# draftBoard.net
KiCad netlist of a schematic drawn in EAGLE
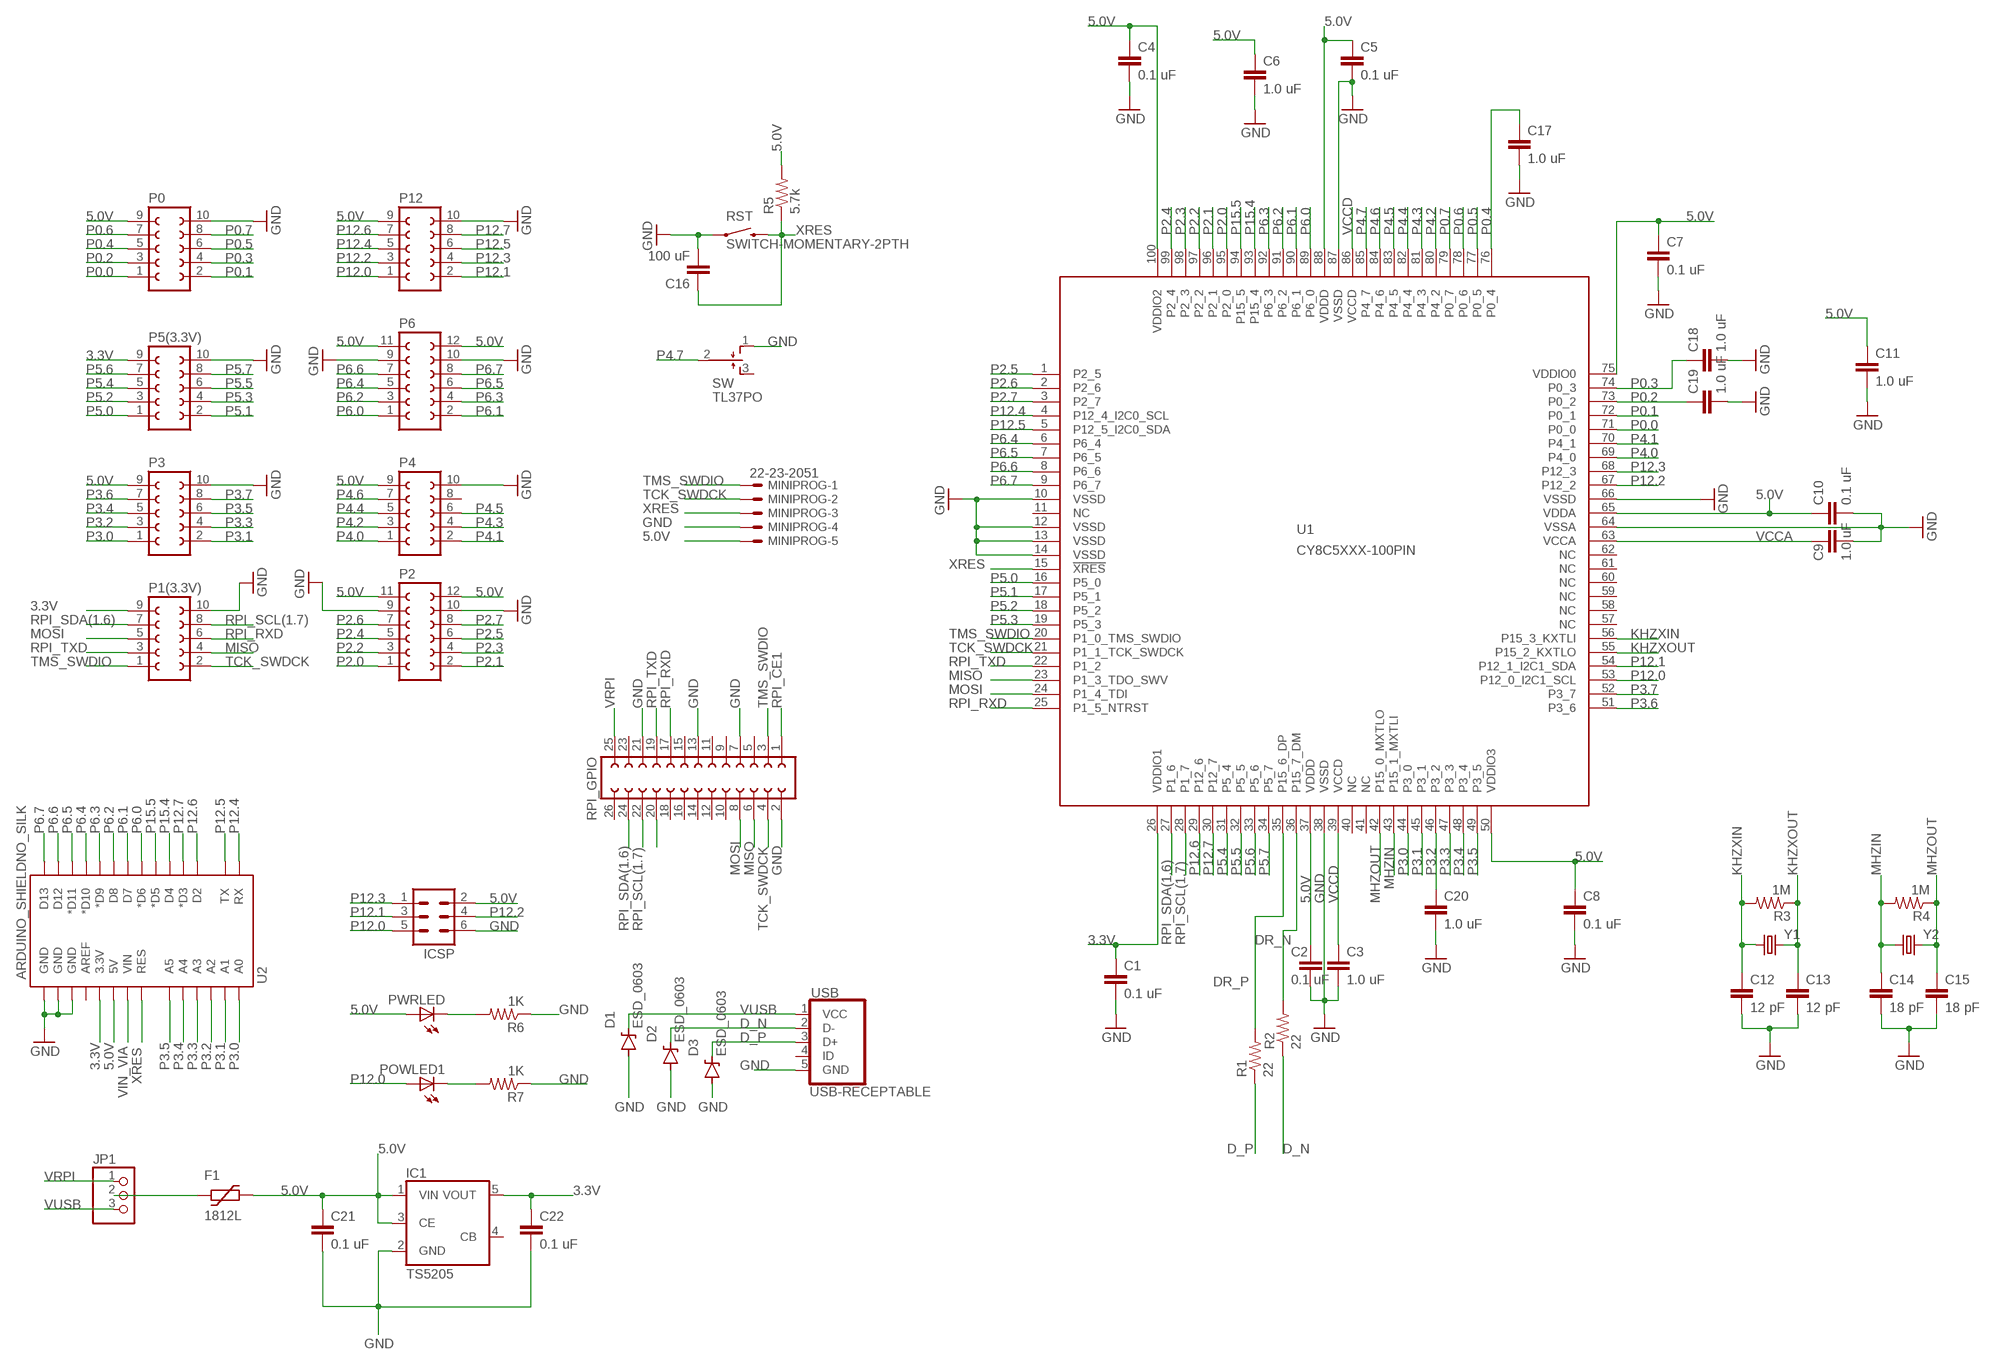
[diagram p0: schematic, sheet 1]

(export (version "E")
  (design (tool "Eeschema 10.0.6"))
  (components
    (comp (ref "C1")
      (value "0.1 uF")
      (footprint "eagle-import:0603-CAP@1")
      (libsource (lib "eagle-import") (part "CAP0603-CAP"))
    )
    (comp (ref "C2")
      (value "0.1 uF")
      (footprint "eagle-import:0603-CAP@1")
      (libsource (lib "eagle-import") (part "CAP0603-CAP"))
    )
    (comp (ref "C3")
      (value "1.0 uF")
      (footprint "eagle-import:0603-CAP@1")
      (libsource (lib "eagle-import") (part "CAP0603-CAP"))
    )
    (comp (ref "C4")
      (value "0.1 uF")
      (footprint "eagle-import:0603-CAP@1")
      (libsource (lib "eagle-import") (part "CAP0603-CAP"))
    )
    (comp (ref "C5")
      (value "0.1 uF")
      (footprint "eagle-import:0603-CAP@1")
      (libsource (lib "eagle-import") (part "CAP0603-CAP"))
    )
    (comp (ref "C6")
      (value "1.0 uF")
      (footprint "eagle-import:0603-CAP@1")
      (libsource (lib "eagle-import") (part "CAP0603-CAP"))
    )
    (comp (ref "C7")
      (value "0.1 uF")
      (footprint "eagle-import:0603-CAP@1")
      (libsource (lib "eagle-import") (part "CAP0603-CAP"))
    )
    (comp (ref "C8")
      (value "0.1 uF")
      (footprint "eagle-import:0603-CAP@1")
      (libsource (lib "eagle-import") (part "CAP0603-CAP"))
    )
    (comp (ref "C9")
      (value "1.0 uF")
      (footprint "eagle-import:0603-CAP@1")
      (libsource (lib "eagle-import") (part "CAP0603-CAP"))
    )
    (comp (ref "C10")
      (value "0.1 uF")
      (footprint "eagle-import:0603-CAP@1")
      (libsource (lib "eagle-import") (part "CAP0603-CAP"))
    )
    (comp (ref "C11")
      (value "1.0 uF")
      (footprint "eagle-import:0603-CAP@1")
      (libsource (lib "eagle-import") (part "CAP0603-CAP"))
    )
    (comp (ref "C12")
      (value "12 pF")
      (footprint "eagle-import:0603-CAP@1")
      (libsource (lib "eagle-import") (part "CAP0603-CAP"))
    )
    (comp (ref "C13")
      (value "12 pF")
      (footprint "eagle-import:0603-CAP@1")
      (libsource (lib "eagle-import") (part "CAP0603-CAP"))
    )
    (comp (ref "C14")
      (value "18 pF")
      (footprint "eagle-import:0603-CAP@1")
      (libsource (lib "eagle-import") (part "CAP0603-CAP"))
    )
    (comp (ref "C15")
      (value "18 pF")
      (footprint "eagle-import:0603-CAP@1")
      (libsource (lib "eagle-import") (part "CAP0603-CAP"))
    )
    (comp (ref "C16")
      (value "100 uF")
      (footprint "eagle-import:0603-CAP@1")
      (libsource (lib "eagle-import") (part "CAP0603-CAP"))
    )
    (comp (ref "C17")
      (value "1.0 uF")
      (footprint "eagle-import:0603-CAP@1")
      (libsource (lib "eagle-import") (part "CAP0603-CAP"))
    )
    (comp (ref "C18")
      (value "1.0 uF")
      (footprint "eagle-import:0603-CAP@1")
      (libsource (lib "eagle-import") (part "CAP0603-CAP"))
    )
    (comp (ref "C19")
      (value "1.0 uF")
      (footprint "eagle-import:0603-CAP@1")
      (libsource (lib "eagle-import") (part "CAP0603-CAP"))
    )
    (comp (ref "C20")
      (value "1.0 uF")
      (footprint "eagle-import:0603-CAP@1")
      (libsource (lib "eagle-import") (part "CAP0603-CAP"))
    )
    (comp (ref "C21")
      (value "0.1 uF")
      (footprint "eagle-import:0603-CAP@1")
      (libsource (lib "eagle-import") (part "CAP0603-CAP"))
    )
    (comp (ref "C22")
      (value "0.1 uF")
      (footprint "eagle-import:0603-CAP@1")
      (libsource (lib "eagle-import") (part "CAP0603-CAP"))
    )
    (comp (ref "D1")
      (value "ESD_0603")
      (footprint "eagle-import:0603-CAP")
      (libsource (lib "eagle-import") (part "ESD_0603"))
    )
    (comp (ref "D2")
      (value "ESD_0603")
      (footprint "eagle-import:0603-CAP")
      (libsource (lib "eagle-import") (part "ESD_0603"))
    )
    (comp (ref "D3")
      (value "ESD_0603")
      (footprint "eagle-import:0603-CAP")
      (libsource (lib "eagle-import") (part "ESD_0603"))
    )
    (comp (ref "F1")
      (value "1812L")
      (footprint "eagle-import:1812L")
      (libsource (lib "eagle-import") (part "1812L"))
    )
    (comp (ref "IC1")
      (value "TS5205")
      (footprint "eagle-import:SOT25")
      (libsource (lib "eagle-import") (part "TS5205"))
    )
    (comp (ref "ICSP")
      (value "MA03-2")
      (footprint "eagle-import:MA03-2")
      (libsource (lib "eagle-import") (part "MA03-2"))
    )
    (comp (ref "JP1")
      (value "PINHD-1X3")
      (footprint "eagle-import:1X03")
      (libsource (lib "eagle-import") (part "PINHD-1X3"))
    )
    (comp (ref "MINIPROG")
      (value "22-23-2051")
      (footprint "eagle-import:22-23-2051")
      (fields (field (name "MF") "MOLEX"))
      (libsource (lib "eagle-import") (part "22-23-2051"))
    )
    (comp (ref "P0")
      (value "FE05-2")
      (footprint "eagle-import:FE05-2")
      (libsource (lib "eagle-import") (part "FE05-2"))
    )
    (comp (ref "P1(3.3V)")
      (value "FE05-2")
      (footprint "eagle-import:FE05-2")
      (libsource (lib "eagle-import") (part "FE05-2"))
    )
    (comp (ref "P2")
      (value "FE06-2")
      (footprint "eagle-import:FE06-2")
      (libsource (lib "eagle-import") (part "FE06-2"))
    )
    (comp (ref "P3")
      (value "FE05-2")
      (footprint "eagle-import:FE05-2")
      (libsource (lib "eagle-import") (part "FE05-2"))
    )
    (comp (ref "P4")
      (value "FE05-2")
      (footprint "eagle-import:FE05-2")
      (libsource (lib "eagle-import") (part "FE05-2"))
    )
    (comp (ref "P5(3.3V)")
      (value "FE05-2")
      (footprint "eagle-import:FE05-2")
      (libsource (lib "eagle-import") (part "FE05-2"))
    )
    (comp (ref "P6")
      (value "FE06-2")
      (footprint "eagle-import:FE06-2")
      (libsource (lib "eagle-import") (part "FE06-2"))
    )
    (comp (ref "P12")
      (value "FE05-2")
      (footprint "eagle-import:FE05-2")
      (libsource (lib "eagle-import") (part "FE05-2"))
    )
    (comp (ref "POWLED1")
      (value "LED0603")
      (footprint "eagle-import:LED-0603")
      (libsource (lib "eagle-import") (part "LED0603"))
    )
    (comp (ref "PWRLED")
      (value "LED0603")
      (footprint "eagle-import:LED-0603")
      (libsource (lib "eagle-import") (part "LED0603"))
    )
    (comp (ref "R1")
      (value "22")
      (footprint "eagle-import:0603-RES")
      (libsource (lib "eagle-import") (part "RESISTOR0603-RES"))
    )
    (comp (ref "R2")
      (value "22")
      (footprint "eagle-import:0603-RES")
      (libsource (lib "eagle-import") (part "RESISTOR0603-RES"))
    )
    (comp (ref "R3")
      (value "1M")
      (footprint "eagle-import:0603-RES")
      (libsource (lib "eagle-import") (part "RESISTOR0603-RES"))
    )
    (comp (ref "R4")
      (value "1M")
      (footprint "eagle-import:0603-RES")
      (libsource (lib "eagle-import") (part "RESISTOR0603-RES"))
    )
    (comp (ref "R5")
      (value "5.7k")
      (footprint "eagle-import:0603-RES")
      (libsource (lib "eagle-import") (part "RESISTOR0603-RES"))
    )
    (comp (ref "R6")
      (value "1K")
      (footprint "eagle-import:0603-RES")
      (libsource (lib "eagle-import") (part "RESISTOR0603-RES"))
    )
    (comp (ref "R7")
      (value "1K")
      (footprint "eagle-import:0603-RES")
      (libsource (lib "eagle-import") (part "RESISTOR0603-RES"))
    )
    (comp (ref "RPI_GPIO")
      (value "FE13-2")
      (footprint "eagle-import:FE13-2")
      (libsource (lib "eagle-import") (part "FE13-2"))
    )
    (comp (ref "RST")
      (value "SWITCH-MOMENTARY-2PTH")
      (footprint "eagle-import:TACTILE-PTH")
      (libsource (lib "eagle-import") (part "SWITCH-MOMENTARY-2PTH"))
    )
    (comp (ref "SW")
      (value "TL37PO")
      (footprint "eagle-import:TL3XPO")
      (libsource (lib "eagle-import") (part "TL37PO"))
    )
    (comp (ref "U1")
      (value "CY8C5XXX-100PIN")
      (footprint "eagle-import:TQFP-14X14-100")
      (fields (field (name "MPN") "CY8C5588AXI-060"))
      (libsource (lib "eagle-import") (part "CY8C5XXX-100PIN"))
    )
    (comp (ref "U2")
      (value "ARDUINO_SHIELDNO_SILK")
      (footprint "eagle-import:DUEMILANOVE_VIAS")
      (libsource (lib "eagle-import") (part "ARDUINO_SHIELDNO_SILK"))
    )
    (comp (ref "USB")
      (value "USB-RECEPTABLE")
      (footprint "eagle-import:FCI-10103594-0001LF")
      (libsource (lib "eagle-import") (part "USB-RECEPTABLE"))
    )
    (comp (ref "Y1")
      (value "CRYSTALTC26H")
      (footprint "eagle-import:TC26H")
      (libsource (lib "eagle-import") (part "CRYSTALTC26H"))
    )
    (comp (ref "Y2")
      (value "CRYSTALHC49US")
      (footprint "eagle-import:HC49US")
      (libsource (lib "eagle-import") (part "CRYSTALHC49US"))
    )
  )
  (nets
    (net (code "1") (name "/3.3V") (class "Default")
      (node (ref "C1") (pin "1") (pinfunction "1_1") (pintype "passive"))
      (node (ref "C22") (pin "1") (pinfunction "1_1") (pintype "passive"))
      (node (ref "IC1") (pin "5") (pinfunction "VOUT_5") (pintype "passive"))
      (node (ref "P1(3.3V)") (pin "9") (pinfunction "9_9") (pintype "passive"))
      (node (ref "P5(3.3V)") (pin "9") (pinfunction "9_9") (pintype "passive"))
      (node (ref "U1") (pin "26") (pinfunction "VDDIO1_26") (pintype "passive"))
      (node (ref "U2") (pin "3.3V") (pinfunction "3.3V_3.3V") (pintype "bidirectional"))
    )
    (net (code "2") (name "/5.0V") (class "Default")
      (node (ref "C10") (pin "1") (pinfunction "1_1") (pintype "passive"))
      (node (ref "C11") (pin "1") (pinfunction "1_1") (pintype "passive"))
      (node (ref "C2") (pin "1") (pinfunction "1_1") (pintype "passive"))
      (node (ref "C21") (pin "1") (pinfunction "1_1") (pintype "passive"))
      (node (ref "C4") (pin "1") (pinfunction "1_1") (pintype "passive"))
      (node (ref "C5") (pin "1") (pinfunction "1_1") (pintype "passive"))
      (node (ref "C6") (pin "1") (pinfunction "1_1") (pintype "passive"))
      (node (ref "C7") (pin "1") (pinfunction "1_1") (pintype "passive"))
      (node (ref "C8") (pin "1") (pinfunction "1_1") (pintype "passive"))
      (node (ref "F1") (pin "P$2") (pinfunction "2_P$2") (pintype "passive"))
      (node (ref "IC1") (pin "1") (pinfunction "VIN_1") (pintype "input"))
      (node (ref "IC1") (pin "3") (pinfunction "CE_3") (pintype "input"))
      (node (ref "ICSP") (pin "2") (pinfunction "2_2") (pintype "passive"))
      (node (ref "MINIPROG") (pin "5") (pinfunction "S_5") (pintype "passive"))
      (node (ref "P0") (pin "9") (pinfunction "9_9") (pintype "passive"))
      (node (ref "P12") (pin "9") (pinfunction "9_9") (pintype "passive"))
      (node (ref "P2") (pin "11") (pinfunction "11_11") (pintype "passive"))
      (node (ref "P2") (pin "12") (pinfunction "12_12") (pintype "passive"))
      (node (ref "P3") (pin "9") (pinfunction "9_9") (pintype "passive"))
      (node (ref "P4") (pin "9") (pinfunction "9_9") (pintype "passive"))
      (node (ref "P6") (pin "11") (pinfunction "11_11") (pintype "passive"))
      (node (ref "P6") (pin "12") (pinfunction "12_12") (pintype "passive"))
      (node (ref "PWRLED") (pin "A") (pinfunction "A_A") (pintype "passive"))
      (node (ref "R5") (pin "2") (pinfunction "2_2") (pintype "passive"))
      (node (ref "U1") (pin "100") (pinfunction "VDDIO2_100") (pintype "passive"))
      (node (ref "U1") (pin "37") (pinfunction "VDDD_37") (pintype "passive"))
      (node (ref "U1") (pin "50") (pinfunction "VDDIO3_50") (pintype "passive"))
      (node (ref "U1") (pin "65") (pinfunction "VDDA_65") (pintype "passive"))
      (node (ref "U1") (pin "75") (pinfunction "VDDIO0_75") (pintype "passive"))
      (node (ref "U1") (pin "88") (pinfunction "VDDD_88") (pintype "passive"))
      (node (ref "U2") (pin "5V") (pinfunction "5V_5V") (pintype "bidirectional"))
    )
    (net (code "3") (name "/DR_N") (class "Default")
      (node (ref "R2") (pin "2") (pinfunction "2_2") (pintype "passive"))
      (node (ref "U1") (pin "36") (pinfunction "P15_7_DM_36") (pintype "passive"))
    )
    (net (code "4") (name "/DR_P") (class "Default")
      (node (ref "R1") (pin "2") (pinfunction "2_2") (pintype "passive"))
      (node (ref "U1") (pin "35") (pinfunction "P15_6_DP_35") (pintype "passive"))
    )
    (net (code "5") (name "/D_N") (class "Default")
      (node (ref "D2") (pin "1") (pinfunction "C_1") (pintype "passive"))
      (node (ref "R2") (pin "1") (pinfunction "1_1") (pintype "passive"))
      (node (ref "USB") (pin "2") (pinfunction "D-_2") (pintype "bidirectional"))
    )
    (net (code "6") (name "/D_P") (class "Default")
      (node (ref "D3") (pin "1") (pinfunction "C_1") (pintype "passive"))
      (node (ref "R1") (pin "1") (pinfunction "1_1") (pintype "passive"))
      (node (ref "USB") (pin "3") (pinfunction "D+_3") (pintype "bidirectional"))
    )
    (net (code "7") (name "/KHZXIN") (class "Default")
      (node (ref "C12") (pin "1") (pinfunction "1_1") (pintype "passive"))
      (node (ref "R3") (pin "2") (pinfunction "2_2") (pintype "passive"))
      (node (ref "U1") (pin "56") (pinfunction "P15_3_KXTLI_56") (pintype "passive"))
      (node (ref "Y1") (pin "1") (pinfunction "1_1") (pintype "passive"))
    )
    (net (code "8") (name "/KHZXOUT") (class "Default")
      (node (ref "C13") (pin "1") (pinfunction "1_1") (pintype "passive"))
      (node (ref "R3") (pin "1") (pinfunction "1_1") (pintype "passive"))
      (node (ref "U1") (pin "55") (pinfunction "P15_2_KXTLO_55") (pintype "passive"))
      (node (ref "Y1") (pin "2") (pinfunction "2_2") (pintype "passive"))
    )
    (net (code "9") (name "/MHZIN") (class "Default")
      (node (ref "C14") (pin "1") (pinfunction "1_1") (pintype "passive"))
      (node (ref "R4") (pin "2") (pinfunction "2_2") (pintype "passive"))
      (node (ref "U1") (pin "43") (pinfunction "P15_1_MXTLI_43") (pintype "passive"))
      (node (ref "Y2") (pin "1") (pinfunction "1_1") (pintype "passive"))
    )
    (net (code "10") (name "/MHZOUT") (class "Default")
      (node (ref "C15") (pin "1") (pinfunction "1_1") (pintype "passive"))
      (node (ref "R4") (pin "1") (pinfunction "1_1") (pintype "passive"))
      (node (ref "U1") (pin "42") (pinfunction "P15_0_MXTLO_42") (pintype "passive"))
      (node (ref "Y2") (pin "2") (pinfunction "2_2") (pintype "passive"))
    )
    (net (code "11") (name "/MISO") (class "Default")
      (node (ref "P1(3.3V)") (pin "4") (pinfunction "4_4") (pintype "passive"))
      (node (ref "RPI_GPIO") (pin "6") (pinfunction "6_6") (pintype "passive"))
      (node (ref "U1") (pin "23") (pinfunction "P1_3_TDO_SWV_23") (pintype "passive"))
    )
    (net (code "12") (name "/MOSI") (class "Default")
      (node (ref "P1(3.3V)") (pin "5") (pinfunction "5_5") (pintype "passive"))
      (node (ref "RPI_GPIO") (pin "8") (pinfunction "8_8") (pintype "passive"))
      (node (ref "U1") (pin "24") (pinfunction "P1_4_TDI_24") (pintype "passive"))
    )
    (net (code "13") (name "/P0.0") (class "Default")
      (node (ref "P0") (pin "1") (pinfunction "1_1") (pintype "passive"))
      (node (ref "U1") (pin "71") (pinfunction "P0_0_71") (pintype "passive"))
    )
    (net (code "14") (name "/P0.1") (class "Default")
      (node (ref "P0") (pin "2") (pinfunction "2_2") (pintype "passive"))
      (node (ref "U1") (pin "72") (pinfunction "P0_1_72") (pintype "passive"))
    )
    (net (code "15") (name "/P0.2") (class "Default")
      (node (ref "C19") (pin "1") (pinfunction "1_1") (pintype "passive"))
      (node (ref "P0") (pin "3") (pinfunction "3_3") (pintype "passive"))
      (node (ref "U1") (pin "73") (pinfunction "P0_2_73") (pintype "passive"))
    )
    (net (code "16") (name "/P0.3") (class "Default")
      (node (ref "C18") (pin "1") (pinfunction "1_1") (pintype "passive"))
      (node (ref "P0") (pin "4") (pinfunction "4_4") (pintype "passive"))
      (node (ref "U1") (pin "74") (pinfunction "P0_3_74") (pintype "passive"))
    )
    (net (code "17") (name "/P0.4") (class "Default")
      (node (ref "C17") (pin "1") (pinfunction "1_1") (pintype "passive"))
      (node (ref "P0") (pin "5") (pinfunction "5_5") (pintype "passive"))
      (node (ref "U1") (pin "76") (pinfunction "P0_4_76") (pintype "passive"))
    )
    (net (code "18") (name "/P0.5") (class "Default")
      (node (ref "P0") (pin "6") (pinfunction "6_6") (pintype "passive"))
      (node (ref "U1") (pin "77") (pinfunction "P0_5_77") (pintype "passive"))
    )
    (net (code "19") (name "/P0.6") (class "Default")
      (node (ref "P0") (pin "7") (pinfunction "7_7") (pintype "passive"))
      (node (ref "U1") (pin "78") (pinfunction "P0_6_78") (pintype "passive"))
    )
    (net (code "20") (name "/P0.7") (class "Default")
      (node (ref "P0") (pin "8") (pinfunction "8_8") (pintype "passive"))
      (node (ref "U1") (pin "79") (pinfunction "P0_7_79") (pintype "passive"))
    )
    (net (code "21") (name "/P2.0") (class "Default")
      (node (ref "P2") (pin "1") (pinfunction "1_1") (pintype "passive"))
      (node (ref "U1") (pin "95") (pinfunction "P2_0_95") (pintype "passive"))
    )
    (net (code "22") (name "/P2.1") (class "Default")
      (node (ref "P2") (pin "2") (pinfunction "2_2") (pintype "passive"))
      (node (ref "U1") (pin "96") (pinfunction "P2_1_96") (pintype "passive"))
    )
    (net (code "23") (name "/P2.2") (class "Default")
      (node (ref "P2") (pin "3") (pinfunction "3_3") (pintype "passive"))
      (node (ref "U1") (pin "97") (pinfunction "P2_2_97") (pintype "passive"))
    )
    (net (code "24") (name "/P2.3") (class "Default")
      (node (ref "P2") (pin "4") (pinfunction "4_4") (pintype "passive"))
      (node (ref "U1") (pin "98") (pinfunction "P2_3_98") (pintype "passive"))
    )
    (net (code "25") (name "/P2.4") (class "Default")
      (node (ref "P2") (pin "5") (pinfunction "5_5") (pintype "passive"))
      (node (ref "U1") (pin "99") (pinfunction "P2_4_99") (pintype "passive"))
    )
    (net (code "26") (name "/P2.5") (class "Default")
      (node (ref "P2") (pin "6") (pinfunction "6_6") (pintype "passive"))
      (node (ref "U1") (pin "1") (pinfunction "P2_5_1") (pintype "passive"))
    )
    (net (code "27") (name "/P2.6") (class "Default")
      (node (ref "P2") (pin "7") (pinfunction "7_7") (pintype "passive"))
      (node (ref "U1") (pin "2") (pinfunction "P2_6_2") (pintype "passive"))
    )
    (net (code "28") (name "/P2.7") (class "Default")
      (node (ref "P2") (pin "8") (pinfunction "8_8") (pintype "passive"))
      (node (ref "U1") (pin "3") (pinfunction "P2_7_3") (pintype "passive"))
    )
    (net (code "29") (name "/P3.0") (class "Default")
      (node (ref "P3") (pin "1") (pinfunction "1_1") (pintype "passive"))
      (node (ref "U1") (pin "44") (pinfunction "P3_0_44") (pintype "passive"))
      (node (ref "U2") (pin "A0") (pinfunction "A0_A0") (pintype "bidirectional"))
    )
    (net (code "30") (name "/P3.1") (class "Default")
      (node (ref "P3") (pin "2") (pinfunction "2_2") (pintype "passive"))
      (node (ref "U1") (pin "45") (pinfunction "P3_1_45") (pintype "passive"))
      (node (ref "U2") (pin "A1") (pinfunction "A1_A1") (pintype "bidirectional"))
    )
    (net (code "31") (name "/P3.2") (class "Default")
      (node (ref "C20") (pin "1") (pinfunction "1_1") (pintype "passive"))
      (node (ref "P3") (pin "3") (pinfunction "3_3") (pintype "passive"))
      (node (ref "U1") (pin "46") (pinfunction "P3_2_46") (pintype "passive"))
      (node (ref "U2") (pin "A2") (pinfunction "A2_A2") (pintype "bidirectional"))
    )
    (net (code "32") (name "/P3.3") (class "Default")
      (node (ref "P3") (pin "4") (pinfunction "4_4") (pintype "passive"))
      (node (ref "U1") (pin "47") (pinfunction "P3_3_47") (pintype "passive"))
      (node (ref "U2") (pin "A3") (pinfunction "A3_A3") (pintype "bidirectional"))
    )
    (net (code "33") (name "/P3.4") (class "Default")
      (node (ref "P3") (pin "5") (pinfunction "5_5") (pintype "passive"))
      (node (ref "U1") (pin "48") (pinfunction "P3_4_48") (pintype "passive"))
      (node (ref "U2") (pin "A4") (pinfunction "A4_A4") (pintype "bidirectional"))
    )
    (net (code "34") (name "/P3.5") (class "Default")
      (node (ref "P3") (pin "6") (pinfunction "6_6") (pintype "passive"))
      (node (ref "U1") (pin "49") (pinfunction "P3_5_49") (pintype "passive"))
      (node (ref "U2") (pin "A5") (pinfunction "A5_A5") (pintype "bidirectional"))
    )
    (net (code "35") (name "/P3.6") (class "Default")
      (node (ref "P3") (pin "7") (pinfunction "7_7") (pintype "passive"))
      (node (ref "U1") (pin "51") (pinfunction "P3_6_51") (pintype "passive"))
    )
    (net (code "36") (name "/P3.7") (class "Default")
      (node (ref "P3") (pin "8") (pinfunction "8_8") (pintype "passive"))
      (node (ref "U1") (pin "52") (pinfunction "P3_7_52") (pintype "passive"))
    )
    (net (code "37") (name "/P4.0") (class "Default")
      (node (ref "P4") (pin "1") (pinfunction "1_1") (pintype "passive"))
      (node (ref "U1") (pin "69") (pinfunction "P4_0_69") (pintype "passive"))
    )
    (net (code "38") (name "/P4.1") (class "Default")
      (node (ref "P4") (pin "2") (pinfunction "2_2") (pintype "passive"))
      (node (ref "U1") (pin "70") (pinfunction "P4_1_70") (pintype "passive"))
    )
    (net (code "39") (name "/P4.2") (class "Default")
      (node (ref "P4") (pin "3") (pinfunction "3_3") (pintype "passive"))
      (node (ref "U1") (pin "80") (pinfunction "P4_2_80") (pintype "passive"))
    )
    (net (code "40") (name "/P4.3") (class "Default")
      (node (ref "P4") (pin "4") (pinfunction "4_4") (pintype "passive"))
      (node (ref "U1") (pin "81") (pinfunction "P4_3_81") (pintype "passive"))
    )
    (net (code "41") (name "/P4.4") (class "Default")
      (node (ref "P4") (pin "5") (pinfunction "5_5") (pintype "passive"))
      (node (ref "U1") (pin "82") (pinfunction "P4_4_82") (pintype "passive"))
    )
    (net (code "42") (name "/P4.5") (class "Default")
      (node (ref "P4") (pin "6") (pinfunction "6_6") (pintype "passive"))
      (node (ref "U1") (pin "83") (pinfunction "P4_5_83") (pintype "passive"))
    )
    (net (code "43") (name "/P4.6") (class "Default")
      (node (ref "P4") (pin "7") (pinfunction "7_7") (pintype "passive"))
      (node (ref "U1") (pin "84") (pinfunction "P4_6_84") (pintype "passive"))
    )
    (net (code "44") (name "/P4.7") (class "Default")
      (node (ref "SW") (pin "2") (pinfunction "P_2") (pintype "passive"))
      (node (ref "U1") (pin "85") (pinfunction "P4_7_85") (pintype "passive"))
    )
    (net (code "45") (name "/P5.0") (class "Default")
      (node (ref "P5(3.3V)") (pin "1") (pinfunction "1_1") (pintype "passive"))
      (node (ref "U1") (pin "16") (pinfunction "P5_0_16") (pintype "passive"))
    )
    (net (code "46") (name "/P5.1") (class "Default")
      (node (ref "P5(3.3V)") (pin "2") (pinfunction "2_2") (pintype "passive"))
      (node (ref "U1") (pin "17") (pinfunction "P5_1_17") (pintype "passive"))
    )
    (net (code "47") (name "/P5.2") (class "Default")
      (node (ref "P5(3.3V)") (pin "3") (pinfunction "3_3") (pintype "passive"))
      (node (ref "U1") (pin "18") (pinfunction "P5_2_18") (pintype "passive"))
    )
    (net (code "48") (name "/P5.3") (class "Default")
      (node (ref "P5(3.3V)") (pin "4") (pinfunction "4_4") (pintype "passive"))
      (node (ref "U1") (pin "19") (pinfunction "P5_3_19") (pintype "passive"))
    )
    (net (code "49") (name "/P5.4") (class "Default")
      (node (ref "P5(3.3V)") (pin "5") (pinfunction "5_5") (pintype "passive"))
      (node (ref "U1") (pin "31") (pinfunction "P5_4_31") (pintype "passive"))
    )
    (net (code "50") (name "/P5.5") (class "Default")
      (node (ref "P5(3.3V)") (pin "6") (pinfunction "6_6") (pintype "passive"))
      (node (ref "U1") (pin "32") (pinfunction "P5_5_32") (pintype "passive"))
    )
    (net (code "51") (name "/P5.6") (class "Default")
      (node (ref "P5(3.3V)") (pin "7") (pinfunction "7_7") (pintype "passive"))
      (node (ref "U1") (pin "33") (pinfunction "P5_6_33") (pintype "passive"))
    )
    (net (code "52") (name "/P5.7") (class "Default")
      (node (ref "P5(3.3V)") (pin "8") (pinfunction "8_8") (pintype "passive"))
      (node (ref "U1") (pin "34") (pinfunction "P5_7_34") (pintype "passive"))
    )
    (net (code "53") (name "/P6.0") (class "Default")
      (node (ref "P6") (pin "1") (pinfunction "1_1") (pintype "passive"))
      (node (ref "U1") (pin "89") (pinfunction "P6_0_89") (pintype "passive"))
      (node (ref "U2") (pin "D6") (pinfunction "*D6_D6") (pintype "bidirectional"))
    )
    (net (code "54") (name "/P6.1") (class "Default")
      (node (ref "P6") (pin "2") (pinfunction "2_2") (pintype "passive"))
      (node (ref "U1") (pin "90") (pinfunction "P6_1_90") (pintype "passive"))
      (node (ref "U2") (pin "D7") (pinfunction "D7_D7") (pintype "bidirectional"))
    )
    (net (code "55") (name "/P6.2") (class "Default")
      (node (ref "P6") (pin "3") (pinfunction "3_3") (pintype "passive"))
      (node (ref "U1") (pin "91") (pinfunction "P6_2_91") (pintype "passive"))
      (node (ref "U2") (pin "D8") (pinfunction "D8_D8") (pintype "bidirectional"))
    )
    (net (code "56") (name "/P6.3") (class "Default")
      (node (ref "P6") (pin "4") (pinfunction "4_4") (pintype "passive"))
      (node (ref "U1") (pin "92") (pinfunction "P6_3_92") (pintype "passive"))
      (node (ref "U2") (pin "D9") (pinfunction "*D9_D9") (pintype "bidirectional"))
    )
    (net (code "57") (name "/P6.4") (class "Default")
      (node (ref "P6") (pin "5") (pinfunction "5_5") (pintype "passive"))
      (node (ref "U1") (pin "6") (pinfunction "P6_4_6") (pintype "passive"))
      (node (ref "U2") (pin "D10") (pinfunction "*D10_D10") (pintype "bidirectional"))
    )
    (net (code "58") (name "/P6.5") (class "Default")
      (node (ref "P6") (pin "6") (pinfunction "6_6") (pintype "passive"))
      (node (ref "U1") (pin "7") (pinfunction "P6_5_7") (pintype "passive"))
      (node (ref "U2") (pin "D11") (pinfunction "*D11_D11") (pintype "bidirectional"))
    )
    (net (code "59") (name "/P6.6") (class "Default")
      (node (ref "P6") (pin "7") (pinfunction "7_7") (pintype "passive"))
      (node (ref "U1") (pin "8") (pinfunction "P6_6_8") (pintype "passive"))
      (node (ref "U2") (pin "D12") (pinfunction "D12_D12") (pintype "bidirectional"))
    )
    (net (code "60") (name "/P6.7") (class "Default")
      (node (ref "P6") (pin "8") (pinfunction "8_8") (pintype "passive"))
      (node (ref "U1") (pin "9") (pinfunction "P6_7_9") (pintype "passive"))
      (node (ref "U2") (pin "D13") (pinfunction "D13_D13") (pintype "bidirectional"))
    )
    (net (code "61") (name "/P12.0") (class "Default")
      (node (ref "ICSP") (pin "5") (pinfunction "5_5") (pintype "passive"))
      (node (ref "P12") (pin "1") (pinfunction "1_1") (pintype "passive"))
      (node (ref "POWLED1") (pin "A") (pinfunction "A_A") (pintype "passive"))
      (node (ref "U1") (pin "53") (pinfunction "P12_0_I2C1_SCL_53") (pintype "passive"))
    )
    (net (code "62") (name "/P12.1") (class "Default")
      (node (ref "ICSP") (pin "3") (pinfunction "3_3") (pintype "passive"))
      (node (ref "P12") (pin "2") (pinfunction "2_2") (pintype "passive"))
      (node (ref "U1") (pin "54") (pinfunction "P12_1_I2C1_SDA_54") (pintype "passive"))
    )
    (net (code "63") (name "/P12.2") (class "Default")
      (node (ref "ICSP") (pin "4") (pinfunction "4_4") (pintype "passive"))
      (node (ref "P12") (pin "3") (pinfunction "3_3") (pintype "passive"))
      (node (ref "U1") (pin "67") (pinfunction "P12_2_67") (pintype "passive"))
    )
    (net (code "64") (name "/P12.3") (class "Default")
      (node (ref "ICSP") (pin "1") (pinfunction "1_1") (pintype "passive"))
      (node (ref "P12") (pin "4") (pinfunction "4_4") (pintype "passive"))
      (node (ref "U1") (pin "68") (pinfunction "P12_3_68") (pintype "passive"))
    )
    (net (code "65") (name "/P12.4") (class "Default")
      (node (ref "P12") (pin "5") (pinfunction "5_5") (pintype "passive"))
      (node (ref "U1") (pin "4") (pinfunction "P12_4_I2C0_SCL_4") (pintype "passive"))
      (node (ref "U2") (pin "RX") (pinfunction "RX_RX") (pintype "bidirectional"))
    )
    (net (code "66") (name "/P12.5") (class "Default")
      (node (ref "P12") (pin "6") (pinfunction "6_6") (pintype "passive"))
      (node (ref "U1") (pin "5") (pinfunction "P12_5_I2C0_SDA_5") (pintype "passive"))
      (node (ref "U2") (pin "TX") (pinfunction "TX_TX") (pintype "bidirectional"))
    )
    (net (code "67") (name "/P12.6") (class "Default")
      (node (ref "P12") (pin "7") (pinfunction "7_7") (pintype "passive"))
      (node (ref "U1") (pin "29") (pinfunction "P12_6_29") (pintype "passive"))
      (node (ref "U2") (pin "D2") (pinfunction "D2_D2") (pintype "bidirectional"))
    )
    (net (code "68") (name "/P12.7") (class "Default")
      (node (ref "P12") (pin "8") (pinfunction "8_8") (pintype "passive"))
      (node (ref "U1") (pin "30") (pinfunction "P12_7_30") (pintype "passive"))
      (node (ref "U2") (pin "D3") (pinfunction "*D3_D3") (pintype "bidirectional"))
    )
    (net (code "69") (name "/P15.4") (class "Default")
      (node (ref "U1") (pin "93") (pinfunction "P15_4_93") (pintype "passive"))
      (node (ref "U2") (pin "D4") (pinfunction "D4_D4") (pintype "bidirectional"))
    )
    (net (code "70") (name "/P15.5") (class "Default")
      (node (ref "U1") (pin "94") (pinfunction "P15_5_94") (pintype "passive"))
      (node (ref "U2") (pin "D5") (pinfunction "*D5_D5") (pintype "bidirectional"))
    )
    (net (code "71") (name "/RPI_CE1") (class "Default")
      (node (ref "RPI_GPIO") (pin "1") (pinfunction "1_1") (pintype "passive"))
    )
    (net (code "72") (name "/RPI_RXD") (class "Default")
      (node (ref "P1(3.3V)") (pin "6") (pinfunction "6_6") (pintype "passive"))
      (node (ref "RPI_GPIO") (pin "17") (pinfunction "17_17") (pintype "passive"))
      (node (ref "U1") (pin "25") (pinfunction "P1_5_NTRST_25") (pintype "passive"))
    )
    (net (code "73") (name "/RPI_SCL(1.7)") (class "Default")
      (node (ref "P1(3.3V)") (pin "8") (pinfunction "8_8") (pintype "passive"))
      (node (ref "RPI_GPIO") (pin "22") (pinfunction "22_22") (pintype "passive"))
      (node (ref "U1") (pin "28") (pinfunction "P1_7_28") (pintype "passive"))
    )
    (net (code "74") (name "/RPI_SDA(1.6)") (class "Default")
      (node (ref "P1(3.3V)") (pin "7") (pinfunction "7_7") (pintype "passive"))
      (node (ref "RPI_GPIO") (pin "24") (pinfunction "24_24") (pintype "passive"))
      (node (ref "U1") (pin "27") (pinfunction "P1_6_27") (pintype "passive"))
    )
    (net (code "75") (name "/RPI_TXD") (class "Default")
      (node (ref "P1(3.3V)") (pin "3") (pinfunction "3_3") (pintype "passive"))
      (node (ref "RPI_GPIO") (pin "19") (pinfunction "19_19") (pintype "passive"))
      (node (ref "U1") (pin "22") (pinfunction "P1_2_22") (pintype "passive"))
    )
    (net (code "76") (name "/TCK_SWDCK") (class "Default")
      (node (ref "MINIPROG") (pin "2") (pinfunction "S_2") (pintype "passive"))
      (node (ref "P1(3.3V)") (pin "2") (pinfunction "2_2") (pintype "passive"))
      (node (ref "RPI_GPIO") (pin "4") (pinfunction "4_4") (pintype "passive"))
      (node (ref "U1") (pin "21") (pinfunction "P1_1_TCK_SWDCK_21") (pintype "passive"))
    )
    (net (code "77") (name "/TMS_SWDIO") (class "Default")
      (node (ref "MINIPROG") (pin "1") (pinfunction "S_1") (pintype "passive"))
      (node (ref "P1(3.3V)") (pin "1") (pinfunction "1_1") (pintype "passive"))
      (node (ref "RPI_GPIO") (pin "3") (pinfunction "3_3") (pintype "passive"))
      (node (ref "U1") (pin "20") (pinfunction "P1_0_TMS_SWDIO_20") (pintype "passive"))
    )
    (net (code "78") (name "/VCCA") (class "Default")
      (node (ref "C9") (pin "1") (pinfunction "1_1") (pintype "passive"))
      (node (ref "U1") (pin "63") (pinfunction "VCCA_63") (pintype "passive"))
    )
    (net (code "79") (name "/VCCD") (class "Default")
      (node (ref "C3") (pin "1") (pinfunction "1_1") (pintype "passive"))
      (node (ref "U1") (pin "39") (pinfunction "VCCD_39") (pintype "passive"))
      (node (ref "U1") (pin "86") (pinfunction "VCCD_86") (pintype "passive"))
    )
    (net (code "80") (name "/VIN_VIA") (class "Default")
      (node (ref "U2") (pin "VIN") (pinfunction "VIN_VIN") (pintype "bidirectional"))
    )
    (net (code "81") (name "/VRPI") (class "Default")
      (node (ref "JP1") (pin "1") (pinfunction "1_1") (pintype "passive"))
      (node (ref "RPI_GPIO") (pin "25") (pinfunction "25_25") (pintype "passive"))
    )
    (net (code "82") (name "/VUSB") (class "Default")
      (node (ref "D1") (pin "1") (pinfunction "C_1") (pintype "passive"))
      (node (ref "JP1") (pin "3") (pinfunction "3_3") (pintype "passive"))
      (node (ref "USB") (pin "1") (pinfunction "VCC_1") (pintype "bidirectional"))
    )
    (net (code "83") (name "/XRES") (class "Default")
      (node (ref "C16") (pin "1") (pinfunction "1_1") (pintype "passive"))
      (node (ref "MINIPROG") (pin "3") (pinfunction "S_3") (pintype "passive"))
      (node (ref "R5") (pin "1") (pinfunction "1_1") (pintype "passive"))
      (node (ref "RST") (pin "3") (pinfunction "2_3") (pintype "passive"))
      (node (ref "U1") (pin "15") (pinfunction "~{XRES}_15") (pintype "passive"))
      (node (ref "U2") (pin "RES") (pinfunction "RES_RES") (pintype "bidirectional"))
    )
    (net (code "84") (name "GND") (class "Default")
      (node (ref "C1") (pin "2") (pinfunction "2_2") (pintype "passive"))
      (node (ref "C10") (pin "2") (pinfunction "2_2") (pintype "passive"))
      (node (ref "C11") (pin "2") (pinfunction "2_2") (pintype "passive"))
      (node (ref "C12") (pin "2") (pinfunction "2_2") (pintype "passive"))
      (node (ref "C13") (pin "2") (pinfunction "2_2") (pintype "passive"))
      (node (ref "C14") (pin "2") (pinfunction "2_2") (pintype "passive"))
      (node (ref "C15") (pin "2") (pinfunction "2_2") (pintype "passive"))
      (node (ref "C16") (pin "2") (pinfunction "2_2") (pintype "passive"))
      (node (ref "C17") (pin "2") (pinfunction "2_2") (pintype "passive"))
      (node (ref "C18") (pin "2") (pinfunction "2_2") (pintype "passive"))
      (node (ref "C19") (pin "2") (pinfunction "2_2") (pintype "passive"))
      (node (ref "C2") (pin "2") (pinfunction "2_2") (pintype "passive"))
      (node (ref "C20") (pin "2") (pinfunction "2_2") (pintype "passive"))
      (node (ref "C21") (pin "2") (pinfunction "2_2") (pintype "passive"))
      (node (ref "C22") (pin "2") (pinfunction "2_2") (pintype "passive"))
      (node (ref "C3") (pin "2") (pinfunction "2_2") (pintype "passive"))
      (node (ref "C4") (pin "2") (pinfunction "2_2") (pintype "passive"))
      (node (ref "C5") (pin "2") (pinfunction "2_2") (pintype "passive"))
      (node (ref "C6") (pin "2") (pinfunction "2_2") (pintype "passive"))
      (node (ref "C7") (pin "2") (pinfunction "2_2") (pintype "passive"))
      (node (ref "C8") (pin "2") (pinfunction "2_2") (pintype "passive"))
      (node (ref "C9") (pin "2") (pinfunction "2_2") (pintype "passive"))
      (node (ref "D1") (pin "2") (pinfunction "A_2") (pintype "passive"))
      (node (ref "D2") (pin "2") (pinfunction "A_2") (pintype "passive"))
      (node (ref "D3") (pin "2") (pinfunction "A_2") (pintype "passive"))
      (node (ref "IC1") (pin "2") (pinfunction "GND_2") (pintype "passive"))
      (node (ref "ICSP") (pin "6") (pinfunction "6_6") (pintype "passive"))
      (node (ref "MINIPROG") (pin "4") (pinfunction "S_4") (pintype "passive"))
      (node (ref "P0") (pin "10") (pinfunction "10_10") (pintype "passive"))
      (node (ref "P1(3.3V)") (pin "10") (pinfunction "10_10") (pintype "passive"))
      (node (ref "P12") (pin "10") (pinfunction "10_10") (pintype "passive"))
      (node (ref "P2") (pin "10") (pinfunction "10_10") (pintype "passive"))
      (node (ref "P2") (pin "9") (pinfunction "9_9") (pintype "passive"))
      (node (ref "P3") (pin "10") (pinfunction "10_10") (pintype "passive"))
      (node (ref "P4") (pin "10") (pinfunction "10_10") (pintype "passive"))
      (node (ref "P5(3.3V)") (pin "10") (pinfunction "10_10") (pintype "passive"))
      (node (ref "P6") (pin "10") (pinfunction "10_10") (pintype "passive"))
      (node (ref "P6") (pin "9") (pinfunction "9_9") (pintype "passive"))
      (node (ref "R6") (pin "1") (pinfunction "1_1") (pintype "passive"))
      (node (ref "R7") (pin "1") (pinfunction "1_1") (pintype "passive"))
      (node (ref "RPI_GPIO") (pin "13") (pinfunction "13_13") (pintype "passive"))
      (node (ref "RPI_GPIO") (pin "2") (pinfunction "2_2") (pintype "passive"))
      (node (ref "RPI_GPIO") (pin "21") (pinfunction "21_21") (pintype "passive"))
      (node (ref "RPI_GPIO") (pin "7") (pinfunction "7_7") (pintype "passive"))
      (node (ref "RST") (pin "1") (pinfunction "1_1") (pintype "passive"))
      (node (ref "SW") (pin "1") (pinfunction "O_1") (pintype "passive"))
      (node (ref "U1") (pin "10") (pinfunction "VSSD_10") (pintype "passive"))
      (node (ref "U1") (pin "12") (pinfunction "VSSD_12") (pintype "passive"))
      (node (ref "U1") (pin "13") (pinfunction "VSSD_13") (pintype "passive"))
      (node (ref "U1") (pin "14") (pinfunction "VSSD_14") (pintype "passive"))
      (node (ref "U1") (pin "38") (pinfunction "VSSD_38") (pintype "passive"))
      (node (ref "U1") (pin "64") (pinfunction "VSSA_64") (pintype "passive"))
      (node (ref "U1") (pin "66") (pinfunction "VSSD_66") (pintype "passive"))
      (node (ref "U1") (pin "87") (pinfunction "VSSD_87") (pintype "passive"))
      (node (ref "U2") (pin "GND@0") (pinfunction "GND_GND@0") (pintype "bidirectional"))
      (node (ref "U2") (pin "GND@1") (pinfunction "GND_GND@1") (pintype "bidirectional"))
      (node (ref "U2") (pin "GND@2") (pinfunction "GND_GND@2") (pintype "bidirectional"))
      (node (ref "USB") (pin "5") (pinfunction "GND_5") (pintype "bidirectional"))
    )
    (net (code "85") (name "Net-(F1-1)") (class "Default")
      (node (ref "F1") (pin "P$1") (pinfunction "1_P$1") (pintype "passive"))
      (node (ref "JP1") (pin "2") (pinfunction "2_2") (pintype "passive"))
    )
    (net (code "86") (name "Net-(POWLED1-PadC)") (class "Default")
      (node (ref "POWLED1") (pin "C") (pinfunction "C_C") (pintype "passive"))
      (node (ref "R7") (pin "2") (pinfunction "2_2") (pintype "passive"))
    )
    (net (code "87") (name "Net-(PWRLED-PadC)") (class "Default")
      (node (ref "PWRLED") (pin "C") (pinfunction "C_C") (pintype "passive"))
      (node (ref "R6") (pin "2") (pinfunction "2_2") (pintype "passive"))
    )
    (net (code "88") (name "unconnected-(IC1-CB-Pad4)") (class "Default")
      (node (ref "IC1") (pin "4") (pinfunction "CB_4") (pintype "input"))
    )
    (net (code "89") (name "unconnected-(P4-Pad8)") (class "Default")
      (node (ref "P4") (pin "8") (pinfunction "8_8") (pintype "passive"))
    )
    (net (code "90") (name "unconnected-(RPI_GPIO-Pad5)") (class "Default")
      (node (ref "RPI_GPIO") (pin "5") (pinfunction "5_5") (pintype "passive"))
    )
    (net (code "91") (name "unconnected-(RPI_GPIO-Pad9)") (class "Default")
      (node (ref "RPI_GPIO") (pin "9") (pinfunction "9_9") (pintype "passive"))
    )
    (net (code "92") (name "unconnected-(RPI_GPIO-Pad10)") (class "Default")
      (node (ref "RPI_GPIO") (pin "10") (pinfunction "10_10") (pintype "passive"))
    )
    (net (code "93") (name "unconnected-(RPI_GPIO-Pad11)") (class "Default")
      (node (ref "RPI_GPIO") (pin "11") (pinfunction "11_11") (pintype "passive"))
    )
    (net (code "94") (name "unconnected-(RPI_GPIO-Pad12)") (class "Default")
      (node (ref "RPI_GPIO") (pin "12") (pinfunction "12_12") (pintype "passive"))
    )
    (net (code "95") (name "unconnected-(RPI_GPIO-Pad14)") (class "Default")
      (node (ref "RPI_GPIO") (pin "14") (pinfunction "14_14") (pintype "passive"))
    )
    (net (code "96") (name "unconnected-(RPI_GPIO-Pad15)") (class "Default")
      (node (ref "RPI_GPIO") (pin "15") (pinfunction "15_15") (pintype "passive"))
    )
    (net (code "97") (name "unconnected-(RPI_GPIO-Pad16)") (class "Default")
      (node (ref "RPI_GPIO") (pin "16") (pinfunction "16_16") (pintype "passive"))
    )
    (net (code "98") (name "unconnected-(RPI_GPIO-Pad18)") (class "Default")
      (node (ref "RPI_GPIO") (pin "18") (pinfunction "18_18") (pintype "passive"))
    )
    (net (code "99") (name "unconnected-(RPI_GPIO-Pad20)") (class "Default")
      (node (ref "RPI_GPIO") (pin "20") (pinfunction "20_20") (pintype "passive"))
    )
    (net (code "100") (name "unconnected-(RPI_GPIO-Pad23)") (class "Default")
      (node (ref "RPI_GPIO") (pin "23") (pinfunction "23_23") (pintype "passive"))
    )
    (net (code "101") (name "unconnected-(RPI_GPIO-Pad26)") (class "Default")
      (node (ref "RPI_GPIO") (pin "26") (pinfunction "26_26") (pintype "passive"))
    )
    (net (code "102") (name "unconnected-(SW-S-Pad3)") (class "Default")
      (node (ref "SW") (pin "3") (pinfunction "S_3") (pintype "passive"))
    )
    (net (code "103") (name "unconnected-(U1-NC-Pad11)") (class "Default")
      (node (ref "U1") (pin "11") (pinfunction "NC_11") (pintype "passive"))
    )
    (net (code "104") (name "unconnected-(U1-NC-Pad40)") (class "Default")
      (node (ref "U1") (pin "40") (pinfunction "NC_40") (pintype "passive"))
    )
    (net (code "105") (name "unconnected-(U1-NC-Pad41)") (class "Default")
      (node (ref "U1") (pin "41") (pinfunction "NC_41") (pintype "passive"))
    )
    (net (code "106") (name "unconnected-(U1-NC-Pad57)") (class "Default")
      (node (ref "U1") (pin "57") (pinfunction "NC_57") (pintype "passive"))
    )
    (net (code "107") (name "unconnected-(U1-NC-Pad58)") (class "Default")
      (node (ref "U1") (pin "58") (pinfunction "NC_58") (pintype "passive"))
    )
    (net (code "108") (name "unconnected-(U1-NC-Pad59)") (class "Default")
      (node (ref "U1") (pin "59") (pinfunction "NC_59") (pintype "passive"))
    )
    (net (code "109") (name "unconnected-(U1-NC-Pad60)") (class "Default")
      (node (ref "U1") (pin "60") (pinfunction "NC_60") (pintype "passive"))
    )
    (net (code "110") (name "unconnected-(U1-NC-Pad61)") (class "Default")
      (node (ref "U1") (pin "61") (pinfunction "NC_61") (pintype "passive"))
    )
    (net (code "111") (name "unconnected-(U1-NC-Pad62)") (class "Default")
      (node (ref "U1") (pin "62") (pinfunction "NC_62") (pintype "passive"))
    )
    (net (code "112") (name "unconnected-(U2-PadAREF)") (class "Default")
      (node (ref "U2") (pin "AREF") (pinfunction "AREF_AREF") (pintype "bidirectional"))
    )
    (net (code "113") (name "unconnected-(USB-ID-Pad4)") (class "Default")
      (node (ref "USB") (pin "4") (pinfunction "ID_4") (pintype "bidirectional"))
    )
  )
)
